# Static_Test_Pad.net
KiCad netlist of a schematic drawn in EAGLE
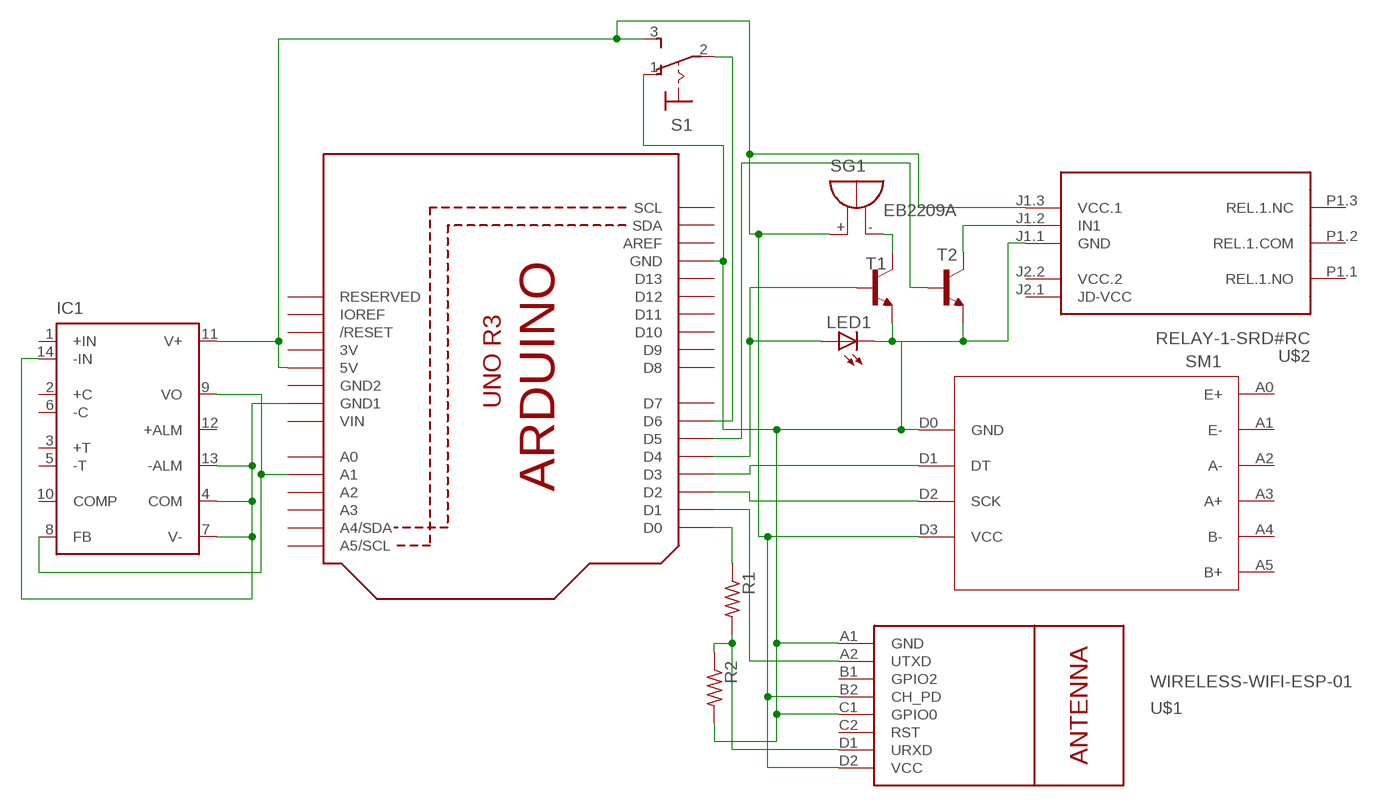
[diagram p0: schematic, sheet 1]

(export (version "E")
  (design (tool "Eeschema 10.0.6"))
  (components
    (comp (ref "IC1")
      (value "AD595")
      (footprint "eagle-import:DIL14")
      (fields (field (name "MPN") "AD595AQ"))
      (libsource (lib "eagle-import") (part "AD595"))
    )
    (comp (ref "LED1")
      (value "LEDB155")
      (footprint "eagle-import:Q62902-B155")
      (libsource (lib "eagle-import") (part "LEDB155"))
    )
    (comp (ref "R1")
      (value "FLIPFLOP-RES")
      (footprint "eagle-import:0805-THM")
      (libsource (lib "eagle-import") (part "FLIPFLOP-RES"))
    )
    (comp (ref "R2")
      (value "FLIPFLOP-RES")
      (footprint "eagle-import:0805-THM")
      (libsource (lib "eagle-import") (part "FLIPFLOP-RES"))
    )
    (comp (ref "S1")
      (value "320-916")
      (footprint "eagle-import:320-916")
      (libsource (lib "eagle-import") (part "320-916"))
    )
    (comp (ref "SG1")
      (value "EB2209A")
      (footprint "eagle-import:EB2209A")
      (libsource (lib "eagle-import") (part "EB2209A"))
    )
    (comp (ref "SM1")
      (value "HX711")
      (footprint "eagle-import:HX711")
      (libsource (lib "eagle-import") (part "HX711"))
    )
    (comp (ref "T1")
      (value "2N3700-NPN-TO18-EBC")
      (footprint "eagle-import:TO18")
      (libsource (lib "eagle-import") (part "-NPN-TO18-EBC2N3700"))
    )
    (comp (ref "T2")
      (value "2N3700-NPN-TO18-EBC")
      (footprint "eagle-import:TO18")
      (libsource (lib "eagle-import") (part "-NPN-TO18-EBC2N3700"))
    )
    (comp (ref "U$1")
      (value "WIRELESS-WIFI-ESP-01")
      (footprint "eagle-import:WIRELESS-WIFI-ESP-01")
      (libsource (lib "eagle-import") (part "WIRELESS-WIFI-ESP-01"))
    )
    (comp (ref "U$2")
      (value "RELAY-1-SRD#RC")
      (footprint "eagle-import:RELAY-1-SRD#RC")
      (libsource (lib "eagle-import") (part "RELAY-1-SRD#RC"))
    )
    (comp (ref "U1")
      (value "ARDUINOR3-BPLACE")
      (footprint "eagle-import:ARDUINOR3-BPLACE")
      (libsource (lib "eagle-import") (part "ARDUINOR3-BPLACE"))
    )
  )
  (nets
    (net (code "1") (name "/3V") (class "Default")
      (node (ref "U1") (pin "3V") (pinfunction "3V_3V") (pintype "power_in"))
    )
    (net (code "2") (name "/GND2") (class "Default")
      (node (ref "U1") (pin "GND2") (pinfunction "GND2_GND2") (pintype "power_in"))
    )
    (net (code "3") (name "/VCC.2") (class "Default")
      (node (ref "U$2") (pin "J2.2") (pinfunction "VCC.2_J2.2") (pintype "power_in"))
    )
    (net (code "4") (name "/VIN") (class "Default")
      (node (ref "U1") (pin "VIN") (pinfunction "VIN_VIN") (pintype "power_in"))
    )
    (net (code "5") (name "Net-(IC1--ALM)") (class "Default")
      (node (ref "IC1") (pin "13") (pinfunction "-ALM_13") (pintype "passive"))
      (node (ref "IC1") (pin "14") (pinfunction "-IN_14") (pintype "input"))
      (node (ref "IC1") (pin "4") (pinfunction "COM_4") (pintype "power_in"))
      (node (ref "IC1") (pin "7") (pinfunction "V-_7") (pintype "power_in"))
      (node (ref "U1") (pin "GND1") (pinfunction "GND1_GND1") (pintype "power_in"))
    )
    (net (code "6") (name "Net-(IC1-FB)") (class "Default")
      (node (ref "IC1") (pin "8") (pinfunction "FB_8") (pintype "passive"))
      (node (ref "IC1") (pin "9") (pinfunction "VO_9") (pintype "output"))
      (node (ref "U1") (pin "A1") (pinfunction "A1_A1") (pintype "bidirectional"))
    )
    (net (code "7") (name "Net-(IC1-V+)") (class "Default")
      (node (ref "IC1") (pin "11") (pinfunction "V+_11") (pintype "power_in"))
      (node (ref "S1") (pin "3") (pinfunction "S_3") (pintype "passive"))
      (node (ref "SG1") (pin "+") (pinfunction "+_+") (pintype "passive"))
      (node (ref "SM1") (pin "D3") (pinfunction "VCC_D3") (pintype "bidirectional"))
      (node (ref "U$1") (pin "B2") (pinfunction "CH_PD_B2") (pintype "bidirectional"))
      (node (ref "U$1") (pin "D2") (pinfunction "VCC_D2") (pintype "power_in"))
      (node (ref "U$2") (pin "J1.3") (pinfunction "VCC.1_J1.3") (pintype "power_in"))
      (node (ref "U1") (pin "5V") (pinfunction "5V_5V") (pintype "power_in"))
    )
    (net (code "8") (name "Net-(LED1-C)") (class "Default")
      (node (ref "LED1") (pin "K") (pinfunction "C_K") (pintype "passive"))
      (node (ref "R2") (pin "2") (pinfunction "2_2") (pintype "passive"))
      (node (ref "S1") (pin "1") (pinfunction "O_1") (pintype "passive"))
      (node (ref "SM1") (pin "D0") (pinfunction "GND_D0") (pintype "bidirectional"))
      (node (ref "T1") (pin "1") (pinfunction "E_1") (pintype "passive"))
      (node (ref "T2") (pin "1") (pinfunction "E_1") (pintype "passive"))
      (node (ref "U$1") (pin "A1") (pinfunction "GND_A1") (pintype "power_in"))
      (node (ref "U$1") (pin "C1") (pinfunction "GPIO0_C1") (pintype "bidirectional"))
      (node (ref "U$2") (pin "J1.1") (pinfunction "GND_J1.1") (pintype "power_in"))
      (node (ref "U1") (pin "GND") (pinfunction "GND_GND") (pintype "power_in"))
    )
    (net (code "9") (name "Net-(R1-Pad1)") (class "Default")
      (node (ref "R1") (pin "1") (pinfunction "1_1") (pintype "passive"))
      (node (ref "U1") (pin "D0") (pinfunction "D0_D0") (pintype "bidirectional"))
    )
    (net (code "10") (name "Net-(S1-P)") (class "Default")
      (node (ref "S1") (pin "2") (pinfunction "P_2") (pintype "passive"))
      (node (ref "U1") (pin "D6") (pinfunction "D6_D6") (pintype "bidirectional"))
    )
    (net (code "11") (name "Net-(SM1-DT)") (class "Default")
      (node (ref "SM1") (pin "D1") (pinfunction "DT_D1") (pintype "bidirectional"))
      (node (ref "U1") (pin "D3") (pinfunction "D3_D3") (pintype "bidirectional"))
    )
    (net (code "12") (name "Net-(SM1-SCK)") (class "Default")
      (node (ref "SM1") (pin "D2") (pinfunction "SCK_D2") (pintype "bidirectional"))
      (node (ref "U1") (pin "D2") (pinfunction "D2_D2") (pintype "bidirectional"))
    )
    (net (code "13") (name "Net-(T1-B)") (class "Default")
      (node (ref "LED1") (pin "A") (pinfunction "A_A") (pintype "passive"))
      (node (ref "T1") (pin "2") (pinfunction "B_2") (pintype "passive"))
      (node (ref "U1") (pin "D4") (pinfunction "D4_D4") (pintype "bidirectional"))
    )
    (net (code "14") (name "Net-(T1-C)") (class "Default")
      (node (ref "SG1") (pin "-") (pinfunction "-_-") (pintype "passive"))
      (node (ref "T1") (pin "3") (pinfunction "C_3") (pintype "passive"))
    )
    (net (code "15") (name "Net-(T2-B)") (class "Default")
      (node (ref "T2") (pin "2") (pinfunction "B_2") (pintype "passive"))
      (node (ref "U1") (pin "D5") (pinfunction "D5_D5") (pintype "bidirectional"))
    )
    (net (code "16") (name "Net-(T2-C)") (class "Default")
      (node (ref "T2") (pin "3") (pinfunction "C_3") (pintype "passive"))
      (node (ref "U$2") (pin "J1.2") (pinfunction "IN1_J1.2") (pintype "bidirectional"))
    )
    (net (code "17") (name "Net-(U$1-URXD)") (class "Default")
      (node (ref "R1") (pin "2") (pinfunction "2_2") (pintype "passive"))
      (node (ref "R2") (pin "1") (pinfunction "1_1") (pintype "passive"))
      (node (ref "U$1") (pin "D1") (pinfunction "URXD_D1") (pintype "bidirectional"))
    )
    (net (code "18") (name "Net-(U$1-UTXD)") (class "Default")
      (node (ref "U$1") (pin "A2") (pinfunction "UTXD_A2") (pintype "bidirectional"))
      (node (ref "U1") (pin "D1") (pinfunction "D1_D1") (pintype "bidirectional"))
    )
    (net (code "19") (name "unconnected-(IC1-+ALM-Pad12)") (class "Default")
      (node (ref "IC1") (pin "12") (pinfunction "+ALM_12") (pintype "passive"))
    )
    (net (code "20") (name "unconnected-(IC1-+C-Pad2)") (class "Default")
      (node (ref "IC1") (pin "2") (pinfunction "+C_2") (pintype "input"))
    )
    (net (code "21") (name "unconnected-(IC1-+IN-Pad1)") (class "Default")
      (node (ref "IC1") (pin "1") (pinfunction "+IN_1") (pintype "input"))
    )
    (net (code "22") (name "unconnected-(IC1-+T-Pad3)") (class "Default")
      (node (ref "IC1") (pin "3") (pinfunction "+T_3") (pintype "passive"))
    )
    (net (code "23") (name "unconnected-(IC1--C-Pad6)") (class "Default")
      (node (ref "IC1") (pin "6") (pinfunction "-C_6") (pintype "input"))
    )
    (net (code "24") (name "unconnected-(IC1--T-Pad5)") (class "Default")
      (node (ref "IC1") (pin "5") (pinfunction "-T_5") (pintype "passive"))
    )
    (net (code "25") (name "unconnected-(IC1-COMP-Pad10)") (class "Default")
      (node (ref "IC1") (pin "10") (pinfunction "COMP_10") (pintype "passive"))
    )
    (net (code "26") (name "unconnected-(SM1-A+-PadA3)") (class "Default")
      (node (ref "SM1") (pin "A3") (pinfunction "A+_A3") (pintype "bidirectional"))
    )
    (net (code "27") (name "unconnected-(SM1-A--PadA2)") (class "Default")
      (node (ref "SM1") (pin "A2") (pinfunction "A-_A2") (pintype "bidirectional"))
    )
    (net (code "28") (name "unconnected-(SM1-B+-PadA5)") (class "Default")
      (node (ref "SM1") (pin "A5") (pinfunction "B+_A5") (pintype "bidirectional"))
    )
    (net (code "29") (name "unconnected-(SM1-B--PadA4)") (class "Default")
      (node (ref "SM1") (pin "A4") (pinfunction "B-_A4") (pintype "bidirectional"))
    )
    (net (code "30") (name "unconnected-(SM1-E+-PadA0)") (class "Default")
      (node (ref "SM1") (pin "A0") (pinfunction "E+_A0") (pintype "bidirectional"))
    )
    (net (code "31") (name "unconnected-(SM1-E--PadA1)") (class "Default")
      (node (ref "SM1") (pin "A1") (pinfunction "E-_A1") (pintype "bidirectional"))
    )
    (net (code "32") (name "unconnected-(U$1-GPIO2-PadB1)") (class "Default")
      (node (ref "U$1") (pin "B1") (pinfunction "GPIO2_B1") (pintype "bidirectional"))
    )
    (net (code "33") (name "unconnected-(U$1-RST-PadC2)") (class "Default")
      (node (ref "U$1") (pin "C2") (pinfunction "RST_C2") (pintype "bidirectional"))
    )
    (net (code "34") (name "unconnected-(U$2-JD-VCC-PadJ2.1)") (class "Default")
      (node (ref "U$2") (pin "J2.1") (pinfunction "JD-VCC_J2.1") (pintype "bidirectional"))
    )
    (net (code "35") (name "unconnected-(U$2-REL.1.COM-PadP1.2)") (class "Default")
      (node (ref "U$2") (pin "P1.2") (pinfunction "REL.1.COM_P1.2") (pintype "bidirectional"))
    )
    (net (code "36") (name "unconnected-(U$2-REL.1.NC-PadP1.3)") (class "Default")
      (node (ref "U$2") (pin "P1.3") (pinfunction "REL.1.NC_P1.3") (pintype "bidirectional"))
    )
    (net (code "37") (name "unconnected-(U$2-REL.1.NO-PadP1.1)") (class "Default")
      (node (ref "U$2") (pin "P1.1") (pinfunction "REL.1.NO_P1.1") (pintype "bidirectional"))
    )
    (net (code "38") (name "unconnected-(U1-A4{slash}SDA-PadA4)") (class "Default")
      (node (ref "U1") (pin "A4") (pinfunction "A4/SDA_A4") (pintype "bidirectional"))
    )
    (net (code "39") (name "unconnected-(U1-A5{slash}SCL-PadA5)") (class "Default")
      (node (ref "U1") (pin "A5") (pinfunction "A5/SCL_A5") (pintype "bidirectional"))
    )
    (net (code "40") (name "unconnected-(U1-PadA0)") (class "Default")
      (node (ref "U1") (pin "A0") (pinfunction "A0_A0") (pintype "bidirectional"))
    )
    (net (code "41") (name "unconnected-(U1-PadA2)") (class "Default")
      (node (ref "U1") (pin "A2") (pinfunction "A2_A2") (pintype "bidirectional"))
    )
    (net (code "42") (name "unconnected-(U1-PadA3)") (class "Default")
      (node (ref "U1") (pin "A3") (pinfunction "A3_A3") (pintype "bidirectional"))
    )
    (net (code "43") (name "unconnected-(U1-PadAREF)") (class "Default")
      (node (ref "U1") (pin "AREF") (pinfunction "AREF_AREF") (pintype "bidirectional"))
    )
    (net (code "44") (name "unconnected-(U1-PadD7)") (class "Default")
      (node (ref "U1") (pin "D7") (pinfunction "D7_D7") (pintype "bidirectional"))
    )
    (net (code "45") (name "unconnected-(U1-PadD8)") (class "Default")
      (node (ref "U1") (pin "D8") (pinfunction "D8_D8") (pintype "bidirectional"))
    )
    (net (code "46") (name "unconnected-(U1-PadD9)") (class "Default")
      (node (ref "U1") (pin "D9") (pinfunction "D9_D9") (pintype "bidirectional"))
    )
    (net (code "47") (name "unconnected-(U1-PadD10)") (class "Default")
      (node (ref "U1") (pin "D10") (pinfunction "D10_D10") (pintype "bidirectional"))
    )
    (net (code "48") (name "unconnected-(U1-PadD11)") (class "Default")
      (node (ref "U1") (pin "D11") (pinfunction "D11_D11") (pintype "bidirectional"))
    )
    (net (code "49") (name "unconnected-(U1-PadD12)") (class "Default")
      (node (ref "U1") (pin "D12") (pinfunction "D12_D12") (pintype "bidirectional"))
    )
    (net (code "50") (name "unconnected-(U1-PadD13)") (class "Default")
      (node (ref "U1") (pin "D13") (pinfunction "D13_D13") (pintype "bidirectional"))
    )
    (net (code "51") (name "unconnected-(U1-PadIOREF)") (class "Default")
      (node (ref "U1") (pin "IOREF") (pinfunction "IOREF_IOREF") (pintype "output"))
    )
    (net (code "52") (name "unconnected-(U1-PadRESERVED)") (class "Default")
      (node (ref "U1") (pin "RESERVED") (pinfunction "RESERVED_RESERVED") (pintype "no_connect"))
    )
    (net (code "53") (name "unconnected-(U1-PadSCL)") (class "Default")
      (node (ref "U1") (pin "SCL") (pinfunction "SCL_SCL") (pintype "bidirectional"))
    )
    (net (code "54") (name "unconnected-(U1-PadSDA)") (class "Default")
      (node (ref "U1") (pin "SDA") (pinfunction "SDA_SDA") (pintype "bidirectional"))
    )
    (net (code "55") (name "unconnected-(U1-{slash}RESET-PadRESET)") (class "Default")
      (node (ref "U1") (pin "RESET") (pinfunction "/RESET_RESET") (pintype "bidirectional"))
    )
  )
)
